# 06_Connectors.net
KiCad netlist of a schematic drawn in Altium Designer
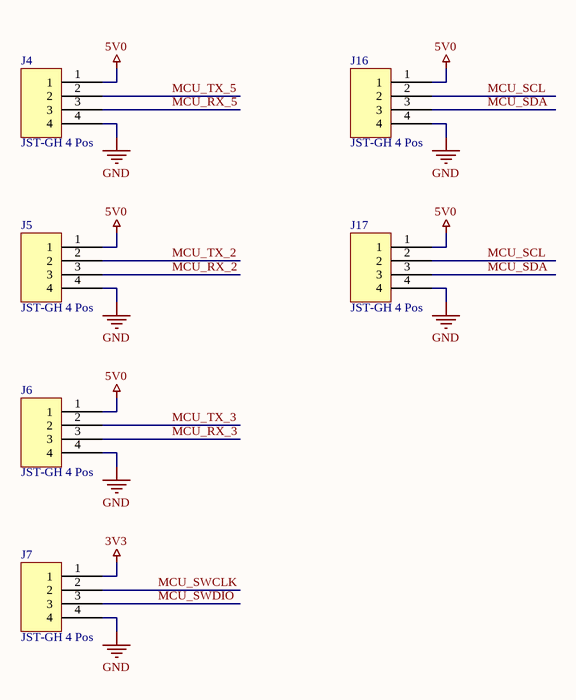
[diagram p0: [06] Connectors.SchDoc]

(export (version "E")
  (design (tool "Eeschema 10.0.6"))
  (components
    (comp (ref "J4")
      (value "JST-GH 4 Pos")
      (footprint "SM04B-GHS-TB(LF)(SN)-")
      (description "JST-GH CONN HEADER SMD R/A 4 POS 1.25MM")
      (fields
        (field (name "MANUFACTURER") "JST")
        (field (name "MANUFACTURER PART NUMBER") "SM04B-GHS-TB(LF)(SN)-")
      )
      (libsource (lib "Connectors") (part "SM04B-GHS-TB(LF)(SN)-"))
    )
    (comp (ref "J5")
      (value "JST-GH 4 Pos")
      (footprint "SM04B-GHS-TB(LF)(SN)-")
      (description "JST-GH CONN HEADER SMD R/A 4 POS 1.25MM")
      (fields
        (field (name "MANUFACTURER") "JST")
        (field (name "MANUFACTURER PART NUMBER") "SM04B-GHS-TB(LF)(SN)-")
      )
      (libsource (lib "Connectors") (part "SM04B-GHS-TB(LF)(SN)-"))
    )
    (comp (ref "J6")
      (value "JST-GH 4 Pos")
      (footprint "SM04B-GHS-TB(LF)(SN)-")
      (description "JST-GH CONN HEADER SMD R/A 4 POS 1.25MM")
      (fields
        (field (name "MANUFACTURER") "JST")
        (field (name "MANUFACTURER PART NUMBER") "SM04B-GHS-TB(LF)(SN)-")
      )
      (libsource (lib "Connectors") (part "SM04B-GHS-TB(LF)(SN)-"))
    )
    (comp (ref "J7")
      (value "JST-GH 4 Pos")
      (footprint "SM04B-GHS-TB(LF)(SN)-")
      (description "JST-GH CONN HEADER SMD R/A 4 POS 1.25MM")
      (fields
        (field (name "MANUFACTURER") "JST")
        (field (name "MANUFACTURER PART NUMBER") "SM04B-GHS-TB(LF)(SN)-")
      )
      (libsource (lib "Connectors") (part "SM04B-GHS-TB(LF)(SN)-"))
    )
    (comp (ref "J16")
      (value "JST-GH 4 Pos")
      (footprint "SM04B-GHS-TB(LF)(SN)-")
      (description "JST-GH CONN HEADER SMD R/A 4 POS 1.25MM")
      (fields
        (field (name "MANUFACTURER") "JST")
        (field (name "MANUFACTURER PART NUMBER") "SM04B-GHS-TB(LF)(SN)-")
      )
      (libsource (lib "Connectors") (part "SM04B-GHS-TB(LF)(SN)-"))
    )
    (comp (ref "J17")
      (value "JST-GH 4 Pos")
      (footprint "SM04B-GHS-TB(LF)(SN)-")
      (description "JST-GH CONN HEADER SMD R/A 4 POS 1.25MM")
      (fields
        (field (name "MANUFACTURER") "JST")
        (field (name "MANUFACTURER PART NUMBER") "SM04B-GHS-TB(LF)(SN)-")
      )
      (libsource (lib "Connectors") (part "SM04B-GHS-TB(LF)(SN)-"))
    )
  )
  (nets
    (net (code "1") (name "/MCU_RX_2") (class "Default")
      (node (ref "J5") (pin "3") (pinfunction "3_3") (pintype "passive"))
    )
    (net (code "2") (name "/MCU_RX_3") (class "Default")
      (node (ref "J6") (pin "3") (pinfunction "3_3") (pintype "passive"))
    )
    (net (code "3") (name "/MCU_RX_5") (class "Default")
      (node (ref "J4") (pin "3") (pinfunction "3_3") (pintype "passive"))
    )
    (net (code "4") (name "/MCU_SCL") (class "Default")
      (node (ref "J16") (pin "2") (pinfunction "2_2") (pintype "passive"))
      (node (ref "J17") (pin "2") (pinfunction "2_2") (pintype "passive"))
    )
    (net (code "5") (name "/MCU_SDA") (class "Default")
      (node (ref "J16") (pin "3") (pinfunction "3_3") (pintype "passive"))
      (node (ref "J17") (pin "3") (pinfunction "3_3") (pintype "passive"))
    )
    (net (code "6") (name "/MCU_SWCLK") (class "Default")
      (node (ref "J7") (pin "2") (pinfunction "2_2") (pintype "passive"))
    )
    (net (code "7") (name "/MCU_SWDIO") (class "Default")
      (node (ref "J7") (pin "3") (pinfunction "3_3") (pintype "passive"))
    )
    (net (code "8") (name "/MCU_TX_2") (class "Default")
      (node (ref "J5") (pin "2") (pinfunction "2_2") (pintype "passive"))
    )
    (net (code "9") (name "/MCU_TX_3") (class "Default")
      (node (ref "J6") (pin "2") (pinfunction "2_2") (pintype "passive"))
    )
    (net (code "10") (name "/MCU_TX_5") (class "Default")
      (node (ref "J4") (pin "2") (pinfunction "2_2") (pintype "passive"))
    )
    (net (code "11") (name "3V3") (class "Default")
      (node (ref "J7") (pin "1") (pinfunction "1_1") (pintype "passive"))
    )
    (net (code "12") (name "5V0") (class "Default")
      (node (ref "J16") (pin "1") (pinfunction "1_1") (pintype "passive"))
      (node (ref "J17") (pin "1") (pinfunction "1_1") (pintype "passive"))
      (node (ref "J4") (pin "1") (pinfunction "1_1") (pintype "passive"))
      (node (ref "J5") (pin "1") (pinfunction "1_1") (pintype "passive"))
      (node (ref "J6") (pin "1") (pinfunction "1_1") (pintype "passive"))
    )
    (net (code "13") (name "GND") (class "Default")
      (node (ref "J16") (pin "4") (pinfunction "4_4") (pintype "passive"))
      (node (ref "J17") (pin "4") (pinfunction "4_4") (pintype "passive"))
      (node (ref "J4") (pin "4") (pinfunction "4_4") (pintype "passive"))
      (node (ref "J5") (pin "4") (pinfunction "4_4") (pintype "passive"))
      (node (ref "J6") (pin "4") (pinfunction "4_4") (pintype "passive"))
      (node (ref "J7") (pin "4") (pinfunction "4_4") (pintype "passive"))
    )
  )
)
